# LPCXpresso55SXX_MCU.net
KiCad netlist of a schematic drawn in Altium Designer
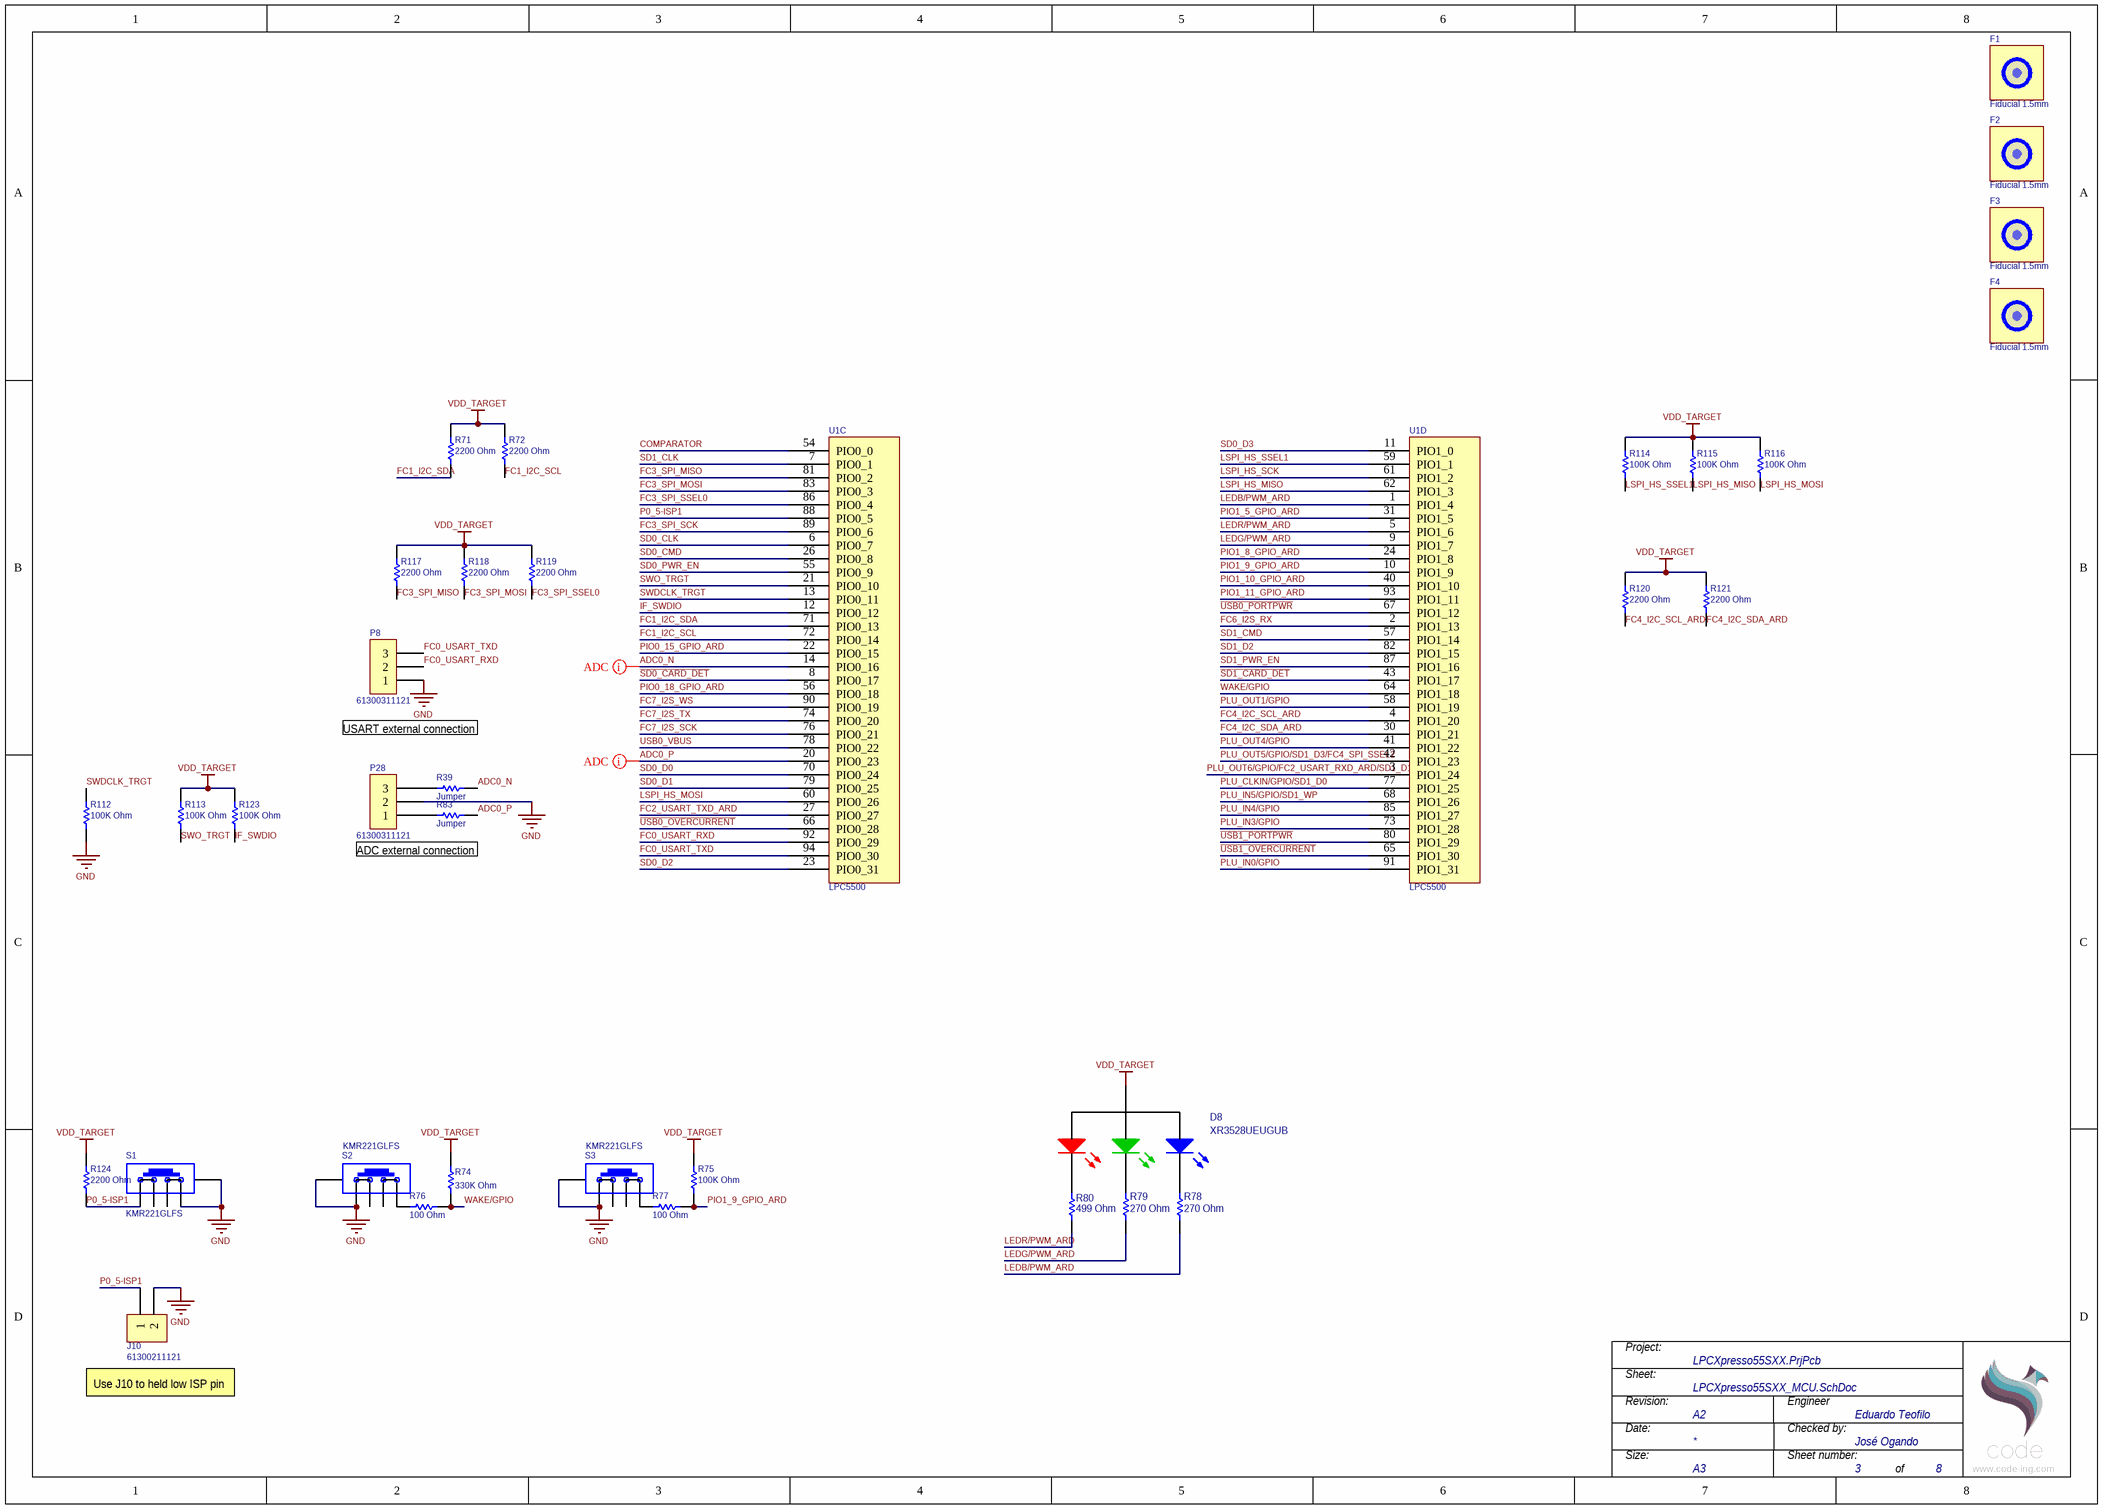
[diagram p0: LPCXpresso55SXX_MCU.SchDoc]

(export (version "E")
  (design (tool "Eeschema 10.0.6"))
  (components
    (comp (ref "D8")
      (value "XR3528UEUGUB")
      (footprint "XR3528UEUGUB")
      (description "LED RGB SMD DIFF 4-PLCC")
      (fields (field (name "CREATED BY") "cmartinez") (field (name "MODIFIED BY") "*"))
      (libsource (lib "LED Indication - Discrete") (part "XR3528UEUGUB"))
    )
    (comp (ref "F1")
      (value "Fiducial 1.5mm")
      (footprint "Fiducial 1.5mm")
      (fields (field (name "CREATED BY") "lsanchez") (field (name "MODIFIED BY") "*"))
      (libsource (lib "Fiducial") (part "Fiducial 1.5mm"))
    )
    (comp (ref "F2")
      (value "Fiducial 1.5mm")
      (footprint "Fiducial 1.5mm")
      (fields (field (name "CREATED BY") "lsanchez") (field (name "MODIFIED BY") "*"))
      (libsource (lib "Fiducial") (part "Fiducial 1.5mm"))
    )
    (comp (ref "F3")
      (value "Fiducial 1.5mm")
      (footprint "Fiducial 1.5mm")
      (fields (field (name "CREATED BY") "lsanchez") (field (name "MODIFIED BY") "*"))
      (libsource (lib "Fiducial") (part "Fiducial 1.5mm"))
    )
    (comp (ref "F4")
      (value "Fiducial 1.5mm")
      (footprint "Fiducial 1.5mm")
      (fields (field (name "CREATED BY") "lsanchez") (field (name "MODIFIED BY") "*"))
      (libsource (lib "Fiducial") (part "Fiducial 1.5mm"))
    )
    (comp (ref "J10")
      (value "61300211121")
      (footprint "61300211121")
      (description "HEADER 2POS SNGL T/H 2.54MM")
      (fields
        (field (name "MANUFACTURER") "Wurth Electronics Inc")
        (field (name "MODIFIED BY") "*")
        (field (name "CREATED BY") "gmoreno")
      )
      (libsource (lib "Rectangular - Headers, Male Pins") (part "61300211121"))
    )
    (comp (ref "P8")
      (value "61300311121")
      (footprint "61300311121")
      (description "HEADER 3POS SNGL T/H 2.54MM")
      (fields
        (field (name "MANUFACTURER") "Wurth Electronics Inc")
        (field (name "MODIFIED BY") "*")
        (field (name "CREATED BY") "gmoreno")
      )
      (libsource (lib "Rectangular - Headers, Male Pins") (part "61300311121"))
    )
    (comp (ref "P28")
      (value "61300311121")
      (footprint "61300311121")
      (description "HEADER 3POS SNGL T/H 2.54MM")
      (fields
        (field (name "MANUFACTURER") "Wurth Electronics Inc")
        (field (name "MODIFIED BY") "*")
        (field (name "CREATED BY") "gmoreno")
      )
      (libsource (lib "Rectangular - Headers, Male Pins") (part "61300311121"))
    )
    (comp (ref "R39")
      (value "Jumper")
      (footprint "RESC0402(1005)_L")
      (description "Jumper 0402 (1005 Metric)")
      (fields (field (name "TOLERANCE") "None"))
      (libsource (lib "Altium Content Vault") (part "CMP-1011-00001-1"))
    )
    (comp (ref "R71")
      (value "2200 Ohm")
      (footprint "RESC0402(1005)_L")
      (description "2K2 0.063W 1% 0402 (1005 Metric)  SMD")
      (fields (field (name "POWER") "0.063 W") (field (name "TOLERANCE") "1 %"))
      (libsource (lib "Altium Content Vault") (part "CMP-1011-00546-1"))
    )
    (comp (ref "R72")
      (value "2200 Ohm")
      (footprint "RESC0402(1005)_L")
      (description "2K2 0.063W 1% 0402 (1005 Metric)  SMD")
      (fields (field (name "POWER") "0.063 W") (field (name "TOLERANCE") "1 %"))
      (libsource (lib "Altium Content Vault") (part "CMP-1011-00546-1"))
    )
    (comp (ref "R74")
      (value "330K Ohm")
      (footprint "RESC0402(1005)_N")
      (description "330K 0.063W 1% 0402 (1005 Metric)  SMD")
      (fields (field (name "POWER") "0.063 W") (field (name "TOLERANCE") "1 %"))
      (libsource (lib "Altium Content Vault") (part "CMP-1011-00793-1"))
    )
    (comp (ref "R75")
      (value "100K Ohm")
      (footprint "RESC1005X40X25LL05T05")
      (description "Chip Resistor, 100 KOhm, +/- 1%, 100 mW, -55 to 155 degC, 0402 (1005 Metric), RoHS, Tape and Reel")
      (fields (field (name "TOLERANCE") "1%") (field (name "MANUFACTURER") "Basic Passives"))
      (libsource (lib "Altium Content Vault") (part "CMP-2002-00608-3"))
    )
    (comp (ref "R76")
      (value "100 Ohm")
      (footprint "RESC0402(1005)_L")
      (description "100R 0.063W 5% 0402 (1005 Metric)  SMD")
      (fields (field (name "POWER") "0.063 W") (field (name "TOLERANCE") "5 %"))
      (libsource (lib "Altium Content Vault") (part "CMP-1011-00050-1"))
    )
    (comp (ref "R77")
      (value "100 Ohm")
      (footprint "RESC0402(1005)_L")
      (description "100R 0.063W 5% 0402 (1005 Metric)  SMD")
      (fields (field (name "POWER") "0.063 W") (field (name "TOLERANCE") "5 %"))
      (libsource (lib "Altium Content Vault") (part "CMP-1011-00050-1"))
    )
    (comp (ref "R78")
      (value "270 Ohm")
      (footprint "RESC0402(1005)_L")
      (description "270R 0.063W 1% 0402 (1005 Metric)  SMD")
      (fields (field (name "TOLERANCE") "1 %") (field (name "POWER") "0.063 W"))
      (libsource (lib "Altium Content Vault") (part "CMP-1011-00444-1"))
    )
    (comp (ref "R79")
      (value "270 Ohm")
      (footprint "RESC0402(1005)_L")
      (description "270R 0.063W 1% 0402 (1005 Metric)  SMD")
      (fields (field (name "TOLERANCE") "1 %") (field (name "POWER") "0.063 W"))
      (libsource (lib "Altium Content Vault") (part "CMP-1011-00444-1"))
    )
    (comp (ref "R80")
      (value "499 Ohm")
      (footprint "RESC0402(1005)_L")
      (description "499R 0.063W 1% 0402 (1005 Metric)  SMD")
      (fields (field (name "TOLERANCE") "1 %") (field (name "POWER") "0.063 W"))
      (libsource (lib "Altium Content Vault") (part "CMP-1011-00476-1"))
    )
    (comp (ref "R83")
      (value "Jumper")
      (footprint "RESC0402(1005)_L")
      (description "Jumper 0402 (1005 Metric)")
      (fields (field (name "TOLERANCE") "None"))
      (libsource (lib "Altium Content Vault") (part "CMP-1011-00001-1"))
    )
    (comp (ref "R112")
      (value "100K Ohm")
      (footprint "RESC1005X40X25LL05T05")
      (description "Chip Resistor, 100 KOhm, +/- 1%, 100 mW, -55 to 155 degC, 0402 (1005 Metric), RoHS, Tape and Reel")
      (fields (field (name "TOLERANCE") "1%") (field (name "MANUFACTURER") "Basic Passives"))
      (libsource (lib "Altium Content Vault") (part "CMP-2002-00608-3"))
    )
    (comp (ref "R113")
      (value "100K Ohm")
      (footprint "RESC1005X40X25LL05T05")
      (description "Chip Resistor, 100 KOhm, +/- 1%, 100 mW, -55 to 155 degC, 0402 (1005 Metric), RoHS, Tape and Reel")
      (fields (field (name "TOLERANCE") "1%") (field (name "MANUFACTURER") "Basic Passives"))
      (libsource (lib "Altium Content Vault") (part "CMP-2002-00608-3"))
    )
    (comp (ref "R114")
      (value "100K Ohm")
      (footprint "RESC1005X40X25LL05T05")
      (description "Chip Resistor, 100 KOhm, +/- 1%, 100 mW, -55 to 155 degC, 0402 (1005 Metric), RoHS, Tape and Reel")
      (fields (field (name "TOLERANCE") "1%") (field (name "MANUFACTURER") "Basic Passives"))
      (libsource (lib "Altium Content Vault") (part "CMP-2002-00608-3"))
    )
    (comp (ref "R115")
      (value "100K Ohm")
      (footprint "RESC1005X40X25LL05T05")
      (description "Chip Resistor, 100 KOhm, +/- 1%, 100 mW, -55 to 155 degC, 0402 (1005 Metric), RoHS, Tape and Reel")
      (fields (field (name "TOLERANCE") "1%") (field (name "MANUFACTURER") "Basic Passives"))
      (libsource (lib "Altium Content Vault") (part "CMP-2002-00608-3"))
    )
    (comp (ref "R116")
      (value "100K Ohm")
      (footprint "RESC1005X40X25LL05T05")
      (description "Chip Resistor, 100 KOhm, +/- 1%, 100 mW, -55 to 155 degC, 0402 (1005 Metric), RoHS, Tape and Reel")
      (fields (field (name "TOLERANCE") "1%") (field (name "MANUFACTURER") "Basic Passives"))
      (libsource (lib "Altium Content Vault") (part "CMP-2002-00608-3"))
    )
    (comp (ref "R117")
      (value "2200 Ohm")
      (footprint "RESC0402(1005)_L")
      (description "2K2 0.063W 1% 0402 (1005 Metric)  SMD")
      (fields (field (name "POWER") "0.063 W") (field (name "TOLERANCE") "1 %"))
      (libsource (lib "Altium Content Vault") (part "CMP-1011-00546-1"))
    )
    (comp (ref "R118")
      (value "2200 Ohm")
      (footprint "RESC0402(1005)_L")
      (description "2K2 0.063W 1% 0402 (1005 Metric)  SMD")
      (fields (field (name "POWER") "0.063 W") (field (name "TOLERANCE") "1 %"))
      (libsource (lib "Altium Content Vault") (part "CMP-1011-00546-1"))
    )
    (comp (ref "R119")
      (value "2200 Ohm")
      (footprint "RESC0402(1005)_L")
      (description "2K2 0.063W 1% 0402 (1005 Metric)  SMD")
      (fields (field (name "POWER") "0.063 W") (field (name "TOLERANCE") "1 %"))
      (libsource (lib "Altium Content Vault") (part "CMP-1011-00546-1"))
    )
    (comp (ref "R120")
      (value "2200 Ohm")
      (footprint "RESC0402(1005)_L")
      (description "2K2 0.063W 1% 0402 (1005 Metric)  SMD")
      (fields (field (name "POWER") "0.063 W") (field (name "TOLERANCE") "1 %"))
      (libsource (lib "Altium Content Vault") (part "CMP-1011-00546-1"))
    )
    (comp (ref "R121")
      (value "2200 Ohm")
      (footprint "RESC0402(1005)_L")
      (description "2K2 0.063W 1% 0402 (1005 Metric)  SMD")
      (fields (field (name "POWER") "0.063 W") (field (name "TOLERANCE") "1 %"))
      (libsource (lib "Altium Content Vault") (part "CMP-1011-00546-1"))
    )
    (comp (ref "R123")
      (value "100K Ohm")
      (footprint "RESC1005X40X25LL05T05")
      (description "Chip Resistor, 100 KOhm, +/- 1%, 100 mW, -55 to 155 degC, 0402 (1005 Metric), RoHS, Tape and Reel")
      (fields (field (name "TOLERANCE") "1%") (field (name "MANUFACTURER") "Basic Passives"))
      (libsource (lib "Altium Content Vault") (part "CMP-2002-00608-3"))
    )
    (comp (ref "R124")
      (value "2200 Ohm")
      (footprint "RESC0402(1005)_L")
      (description "2K2 0.063W 1% 0402 (1005 Metric)  SMD")
      (fields (field (name "POWER") "0.063 W") (field (name "TOLERANCE") "1 %"))
      (libsource (lib "Altium Content Vault") (part "CMP-1011-00546-1"))
    )
    (comp (ref "S1")
      (value "KMR221GLFS")
      (footprint "KMR221GLFS")
      (description "SWITCH TACTILE SPST-NO 0.05A 32V")
      (fields
        (field (name "MANUFACTURER") "C&K")
        (field (name "CREATED BY") "eteofilo")
        (field (name "MODIFIED BY") "*")
      )
      (libsource (lib "Tactile") (part "KMR221GLFS"))
    )
    (comp (ref "S2")
      (value "KMR221GLFS")
      (footprint "KMR221GLFS")
      (description "SWITCH TACTILE SPST-NO 0.05A 32V")
      (fields
        (field (name "MANUFACTURER") "C&K")
        (field (name "CREATED BY") "eteofilo")
        (field (name "MODIFIED BY") "*")
      )
      (libsource (lib "") (part "KMR221GLFS_1"))
    )
    (comp (ref "S3")
      (value "KMR221GLFS")
      (footprint "KMR221GLFS")
      (description "SWITCH TACTILE SPST-NO 0.05A 32V")
      (fields
        (field (name "MANUFACTURER") "C&K")
        (field (name "CREATED BY") "eteofilo")
        (field (name "MODIFIED BY") "*")
      )
      (libsource (lib "") (part "KMR221GLFS_1"))
    )
    (comp (ref "U1")
      (value "LPC5500")
      (footprint "LQFP EP 100")
      (description "32-bit ARM Cortex-M33, 312 KB SRAM, LPC55XX Series")
      (fields
        (field (name "MANUFACTURER") "NXP")
        (field (name "CREATED BY") "eteofilo")
        (field (name "MODIFIED BY") "*")
      )
      (libsource (lib "Embedded - Microcontrollers") (part "LPC5500"))
    )
  )
  (nets
    (net (code "1") (name "/ADC0_N") (class "Default")
      (node (ref "R39") (pin "1") (pinfunction "1_1") (pintype "passive"))
      (node (ref "U1") (pin "14") (pinfunction "PIO0_16_14") (pintype "passive"))
    )
    (net (code "2") (name "/ADC0_P") (class "Default")
      (node (ref "R83") (pin "1") (pinfunction "1_1") (pintype "passive"))
      (node (ref "U1") (pin "20") (pinfunction "PIO0_23_20") (pintype "passive"))
    )
    (net (code "3") (name "/COMPARATOR") (class "Default")
      (node (ref "U1") (pin "54") (pinfunction "PIO0_0_54") (pintype "passive"))
    )
    (net (code "4") (name "/FC0_USART_RXD") (class "Default")
      (node (ref "P8") (pin "2") (pinfunction "2_2") (pintype "passive"))
      (node (ref "U1") (pin "92") (pinfunction "PIO0_29_92") (pintype "passive"))
    )
    (net (code "5") (name "/FC0_USART_TXD") (class "Default")
      (node (ref "P8") (pin "3") (pinfunction "3_3") (pintype "passive"))
      (node (ref "U1") (pin "94") (pinfunction "PIO0_30_94") (pintype "passive"))
    )
    (net (code "6") (name "/FC1_I2C_SCL") (class "Default")
      (node (ref "R72") (pin "1") (pinfunction "1_1") (pintype "passive"))
      (node (ref "U1") (pin "72") (pinfunction "PIO0_14_72") (pintype "passive"))
    )
    (net (code "7") (name "/FC1_I2C_SDA") (class "Default")
      (node (ref "R71") (pin "1") (pinfunction "1_1") (pintype "passive"))
      (node (ref "U1") (pin "71") (pinfunction "PIO0_13_71") (pintype "passive"))
    )
    (net (code "8") (name "/FC2_USART_TXD_ARD") (class "Default")
      (node (ref "U1") (pin "27") (pinfunction "PIO0_27_27") (pintype "passive"))
    )
    (net (code "9") (name "/FC3_SPI_MISO") (class "Default")
      (node (ref "R117") (pin "1") (pinfunction "1_1") (pintype "passive"))
      (node (ref "U1") (pin "81") (pinfunction "PIO0_2_81") (pintype "passive"))
    )
    (net (code "10") (name "/FC3_SPI_MOSI") (class "Default")
      (node (ref "R118") (pin "1") (pinfunction "1_1") (pintype "passive"))
      (node (ref "U1") (pin "83") (pinfunction "PIO0_3_83") (pintype "passive"))
    )
    (net (code "11") (name "/FC3_SPI_SCK") (class "Default")
      (node (ref "U1") (pin "89") (pinfunction "PIO0_6_89") (pintype "passive"))
    )
    (net (code "12") (name "/FC3_SPI_SSEL0") (class "Default")
      (node (ref "R119") (pin "1") (pinfunction "1_1") (pintype "passive"))
      (node (ref "U1") (pin "86") (pinfunction "PIO0_4_86") (pintype "passive"))
    )
    (net (code "13") (name "/FC4_I2C_SCL_ARD") (class "Default")
      (node (ref "R120") (pin "1") (pinfunction "1_1") (pintype "passive"))
      (node (ref "U1") (pin "4") (pinfunction "PIO1_20_4") (pintype "passive"))
    )
    (net (code "14") (name "/FC4_I2C_SDA_ARD") (class "Default")
      (node (ref "R121") (pin "1") (pinfunction "1_1") (pintype "passive"))
      (node (ref "U1") (pin "30") (pinfunction "PIO1_21_30") (pintype "passive"))
    )
    (net (code "15") (name "/FC6_I2S_RX") (class "Default")
      (node (ref "U1") (pin "2") (pinfunction "PIO1_13_2") (pintype "passive"))
    )
    (net (code "16") (name "/FC7_I2S_SCK") (class "Default")
      (node (ref "U1") (pin "76") (pinfunction "PIO0_21_76") (pintype "passive"))
    )
    (net (code "17") (name "/FC7_I2S_TX") (class "Default")
      (node (ref "U1") (pin "74") (pinfunction "PIO0_20_74") (pintype "passive"))
    )
    (net (code "18") (name "/FC7_I2S_WS") (class "Default")
      (node (ref "U1") (pin "90") (pinfunction "PIO0_19_90") (pintype "passive"))
    )
    (net (code "19") (name "/IF_SWDIO") (class "Default")
      (node (ref "R123") (pin "1") (pinfunction "1_1") (pintype "passive"))
      (node (ref "U1") (pin "12") (pinfunction "PIO0_12_12") (pintype "passive"))
    )
    (net (code "20") (name "/LEDB{slash}PWM_ARD") (class "Default")
      (node (ref "R78") (pin "1") (pinfunction "1_1") (pintype "passive"))
      (node (ref "U1") (pin "1") (pinfunction "PIO1_4_1") (pintype "passive"))
    )
    (net (code "21") (name "/LEDG{slash}PWM_ARD") (class "Default")
      (node (ref "R79") (pin "1") (pinfunction "1_1") (pintype "passive"))
      (node (ref "U1") (pin "9") (pinfunction "PIO1_7_9") (pintype "passive"))
    )
    (net (code "22") (name "/LEDR{slash}PWM_ARD") (class "Default")
      (node (ref "R80") (pin "1") (pinfunction "1_1") (pintype "passive"))
      (node (ref "U1") (pin "5") (pinfunction "PIO1_6_5") (pintype "passive"))
    )
    (net (code "23") (name "/LSPI_HS_MISO") (class "Default")
      (node (ref "R115") (pin "1") (pinfunction "1_1") (pintype "passive"))
      (node (ref "U1") (pin "62") (pinfunction "PIO1_3_62") (pintype "passive"))
    )
    (net (code "24") (name "/LSPI_HS_MOSI") (class "Default")
      (node (ref "R116") (pin "1") (pinfunction "1_1") (pintype "passive"))
      (node (ref "U1") (pin "60") (pinfunction "PIO0_26_60") (pintype "passive"))
    )
    (net (code "25") (name "/LSPI_HS_SCK") (class "Default")
      (node (ref "U1") (pin "61") (pinfunction "PIO1_2_61") (pintype "passive"))
    )
    (net (code "26") (name "/LSPI_HS_SSEL1") (class "Default")
      (node (ref "R114") (pin "1") (pinfunction "1_1") (pintype "passive"))
      (node (ref "U1") (pin "59") (pinfunction "PIO1_1_59") (pintype "passive"))
    )
    (net (code "27") (name "/P0_5-ISP1") (class "Default")
      (node (ref "J10") (pin "1") (pinfunction "1_1") (pintype "passive"))
      (node (ref "R124") (pin "2") (pinfunction "2_2") (pintype "passive"))
      (node (ref "S1") (pin "1") (pinfunction "1_1") (pintype "passive"))
      (node (ref "U1") (pin "88") (pinfunction "PIO0_5_88") (pintype "passive"))
    )
    (net (code "28") (name "/PIO0_15_GPIO_ARD") (class "Default")
      (node (ref "U1") (pin "22") (pinfunction "PIO0_15_22") (pintype "passive"))
    )
    (net (code "29") (name "/PIO0_18_GPIO_ARD") (class "Default")
      (node (ref "U1") (pin "56") (pinfunction "PIO0_18_56") (pintype "passive"))
    )
    (net (code "30") (name "/PIO1_5_GPIO_ARD") (class "Default")
      (node (ref "U1") (pin "31") (pinfunction "PIO1_5_31") (pintype "passive"))
    )
    (net (code "31") (name "/PIO1_8_GPIO_ARD") (class "Default")
      (node (ref "U1") (pin "24") (pinfunction "PIO1_8_24") (pintype "passive"))
    )
    (net (code "32") (name "/PIO1_9_GPIO_ARD") (class "Default")
      (node (ref "R75") (pin "1") (pinfunction "1_1") (pintype "passive"))
      (node (ref "R77") (pin "2") (pinfunction "2_2") (pintype "passive"))
      (node (ref "U1") (pin "10") (pinfunction "PIO1_9_10") (pintype "passive"))
    )
    (net (code "33") (name "/PIO1_10_GPIO_ARD") (class "Default")
      (node (ref "U1") (pin "40") (pinfunction "PIO1_10_40") (pintype "passive"))
    )
    (net (code "34") (name "/PIO1_11_GPIO_ARD") (class "Default")
      (node (ref "U1") (pin "93") (pinfunction "PIO1_11_93") (pintype "passive"))
    )
    (net (code "35") (name "/PLU_CLKIN{slash}GPIO{slash}SD1_D0") (class "Default")
      (node (ref "U1") (pin "77") (pinfunction "PIO1_25_77") (pintype "passive"))
    )
    (net (code "36") (name "/PLU_IN0{slash}GPIO") (class "Default")
      (node (ref "U1") (pin "91") (pinfunction "PIO1_31_91") (pintype "passive"))
    )
    (net (code "37") (name "/PLU_IN3{slash}GPIO") (class "Default")
      (node (ref "U1") (pin "73") (pinfunction "PIO1_28_73") (pintype "passive"))
    )
    (net (code "38") (name "/PLU_IN4{slash}GPIO") (class "Default")
      (node (ref "U1") (pin "85") (pinfunction "PIO1_27_85") (pintype "passive"))
    )
    (net (code "39") (name "/PLU_IN5{slash}GPIO{slash}SD1_WP") (class "Default")
      (node (ref "U1") (pin "68") (pinfunction "PIO1_26_68") (pintype "passive"))
    )
    (net (code "40") (name "/PLU_OUT1{slash}GPIO") (class "Default")
      (node (ref "U1") (pin "58") (pinfunction "PIO1_19_58") (pintype "passive"))
    )
    (net (code "41") (name "/PLU_OUT4{slash}GPIO") (class "Default")
      (node (ref "U1") (pin "41") (pinfunction "PIO1_22_41") (pintype "passive"))
    )
    (net (code "42") (name "/PLU_OUT5{slash}GPIO{slash}SD1_D3{slash}FC4_SPI_SSEL2") (class "Default")
      (node (ref "U1") (pin "42") (pinfunction "PIO1_23_42") (pintype "passive"))
    )
    (net (code "43") (name "/PLU_OUT6{slash}GPIO{slash}FC2_USART_RXD_ARD{slash}SD1_D1") (class "Default")
      (node (ref "U1") (pin "3") (pinfunction "PIO1_24_3") (pintype "passive"))
    )
    (net (code "44") (name "/SD0_CLK") (class "Default")
      (node (ref "U1") (pin "6") (pinfunction "PIO0_7_6") (pintype "passive"))
    )
    (net (code "45") (name "/SD0_CMD") (class "Default")
      (node (ref "U1") (pin "26") (pinfunction "PIO0_8_26") (pintype "passive"))
    )
    (net (code "46") (name "/SD0_D0") (class "Default")
      (node (ref "U1") (pin "70") (pinfunction "PIO0_24_70") (pintype "passive"))
    )
    (net (code "47") (name "/SD0_D1") (class "Default")
      (node (ref "U1") (pin "79") (pinfunction "PIO0_25_79") (pintype "passive"))
    )
    (net (code "48") (name "/SD0_D2") (class "Default")
      (node (ref "U1") (pin "23") (pinfunction "PIO0_31_23") (pintype "passive"))
    )
    (net (code "49") (name "/SD0_D3") (class "Default")
      (node (ref "U1") (pin "11") (pinfunction "PIO1_0_11") (pintype "passive"))
    )
    (net (code "50") (name "/SD0_PWR_EN") (class "Default")
      (node (ref "U1") (pin "55") (pinfunction "PIO0_9_55") (pintype "passive"))
    )
    (net (code "51") (name "/SD1_CLK") (class "Default")
      (node (ref "U1") (pin "7") (pinfunction "PIO0_1_7") (pintype "passive"))
    )
    (net (code "52") (name "/SD1_CMD") (class "Default")
      (node (ref "U1") (pin "57") (pinfunction "PIO1_14_57") (pintype "passive"))
    )
    (net (code "53") (name "/SD1_D2") (class "Default")
      (node (ref "U1") (pin "82") (pinfunction "PIO1_15_82") (pintype "passive"))
    )
    (net (code "54") (name "/SD1_PWR_EN") (class "Default")
      (node (ref "U1") (pin "87") (pinfunction "PIO1_16_87") (pintype "passive"))
    )
    (net (code "55") (name "/SWDCLK_TRGT") (class "Default")
      (node (ref "R112") (pin "2") (pinfunction "2_2") (pintype "passive"))
      (node (ref "U1") (pin "13") (pinfunction "PIO0_11_13") (pintype "passive"))
    )
    (net (code "56") (name "/SWO_TRGT") (class "Default")
      (node (ref "R113") (pin "1") (pinfunction "1_1") (pintype "passive"))
      (node (ref "U1") (pin "21") (pinfunction "PIO0_10_21") (pintype "passive"))
    )
    (net (code "57") (name "/USB0_VBUS") (class "Default")
      (node (ref "U1") (pin "78") (pinfunction "PIO0_22_78") (pintype "passive"))
    )
    (net (code "58") (name "/WAKE{slash}GPIO") (class "Default")
      (node (ref "R74") (pin "1") (pinfunction "1_1") (pintype "passive"))
      (node (ref "R76") (pin "2") (pinfunction "2_2") (pintype "passive"))
      (node (ref "U1") (pin "64") (pinfunction "PIO1_18_64") (pintype "passive"))
    )
    (net (code "59") (name "/~{SD0_CARD_DET}") (class "Default")
      (node (ref "U1") (pin "8") (pinfunction "PIO0_17_8") (pintype "passive"))
    )
    (net (code "60") (name "/~{SD1_CARD_DET}") (class "Default")
      (node (ref "U1") (pin "43") (pinfunction "PIO1_17_43") (pintype "passive"))
    )
    (net (code "61") (name "/~{USB0_OVERCURRENT}") (class "Default")
      (node (ref "U1") (pin "66") (pinfunction "PIO0_28_66") (pintype "passive"))
    )
    (net (code "62") (name "/~{USB0_PORTPWR}") (class "Default")
      (node (ref "U1") (pin "67") (pinfunction "PIO1_12_67") (pintype "passive"))
    )
    (net (code "63") (name "/~{USB1_OVERCURRENT}") (class "Default")
      (node (ref "U1") (pin "65") (pinfunction "PIO1_30_65") (pintype "passive"))
    )
    (net (code "64") (name "/~{USB1_PORTPWR}") (class "Default")
      (node (ref "U1") (pin "80") (pinfunction "PIO1_29_80") (pintype "passive"))
    )
    (net (code "65") (name "GND") (class "Default")
      (node (ref "J10") (pin "2") (pinfunction "2_2") (pintype "passive"))
      (node (ref "P28") (pin "2") (pinfunction "2_2") (pintype "passive"))
      (node (ref "P8") (pin "1") (pinfunction "1_1") (pintype "passive"))
      (node (ref "R112") (pin "1") (pinfunction "1_1") (pintype "passive"))
      (node (ref "S1") (pin "2") (pinfunction "2_2") (pintype "passive"))
      (node (ref "S1") (pin "5") (pinfunction "5_5") (pintype "passive"))
      (node (ref "S2") (pin "2") (pinfunction "2_2") (pintype "passive"))
      (node (ref "S2") (pin "5") (pinfunction "5_5") (pintype "passive"))
      (node (ref "S3") (pin "2") (pinfunction "2_2") (pintype "passive"))
      (node (ref "S3") (pin "5") (pinfunction "5_5") (pintype "passive"))
    )
    (net (code "66") (name "Net-(D8-Pad1)") (class "Default")
      (node (ref "D8") (pin "1") (pinfunction "1_1") (pintype "passive"))
      (node (ref "R78") (pin "2") (pinfunction "2_2") (pintype "passive"))
    )
    (net (code "67") (name "Net-(D8-Pad3)") (class "Default")
      (node (ref "D8") (pin "3") (pinfunction "3_3") (pintype "passive"))
      (node (ref "R80") (pin "2") (pinfunction "2_2") (pintype "passive"))
    )
    (net (code "68") (name "Net-(D8-Pad4)") (class "Default")
      (node (ref "D8") (pin "4") (pinfunction "4_4") (pintype "passive"))
      (node (ref "R79") (pin "2") (pinfunction "2_2") (pintype "passive"))
    )
    (net (code "69") (name "Net-(P28-Pad1)") (class "Default")
      (node (ref "P28") (pin "1") (pinfunction "1_1") (pintype "passive"))
      (node (ref "R83") (pin "2") (pinfunction "2_2") (pintype "passive"))
    )
    (net (code "70") (name "Net-(P28-Pad3)") (class "Default")
      (node (ref "P28") (pin "3") (pinfunction "3_3") (pintype "passive"))
      (node (ref "R39") (pin "2") (pinfunction "2_2") (pintype "passive"))
    )
    (net (code "71") (name "Net-(R76-Pad1)") (class "Default")
      (node (ref "R76") (pin "1") (pinfunction "1_1") (pintype "passive"))
      (node (ref "S2") (pin "1") (pinfunction "1_1") (pintype "passive"))
    )
    (net (code "72") (name "Net-(R77-Pad1)") (class "Default")
      (node (ref "R77") (pin "1") (pinfunction "1_1") (pintype "passive"))
      (node (ref "S3") (pin "1") (pinfunction "1_1") (pintype "passive"))
    )
    (net (code "73") (name "VDD_TARGET") (class "Default")
      (node (ref "D8") (pin "2") (pinfunction "2_2") (pintype "passive"))
      (node (ref "R113") (pin "2") (pinfunction "2_2") (pintype "passive"))
      (node (ref "R114") (pin "2") (pinfunction "2_2") (pintype "passive"))
      (node (ref "R115") (pin "2") (pinfunction "2_2") (pintype "passive"))
      (node (ref "R116") (pin "2") (pinfunction "2_2") (pintype "passive"))
      (node (ref "R117") (pin "2") (pinfunction "2_2") (pintype "passive"))
      (node (ref "R118") (pin "2") (pinfunction "2_2") (pintype "passive"))
      (node (ref "R119") (pin "2") (pinfunction "2_2") (pintype "passive"))
      (node (ref "R120") (pin "2") (pinfunction "2_2") (pintype "passive"))
      (node (ref "R121") (pin "2") (pinfunction "2_2") (pintype "passive"))
      (node (ref "R123") (pin "2") (pinfunction "2_2") (pintype "passive"))
      (node (ref "R124") (pin "1") (pinfunction "1_1") (pintype "passive"))
      (node (ref "R71") (pin "2") (pinfunction "2_2") (pintype "passive"))
      (node (ref "R72") (pin "2") (pinfunction "2_2") (pintype "passive"))
      (node (ref "R74") (pin "2") (pinfunction "2_2") (pintype "passive"))
      (node (ref "R75") (pin "2") (pinfunction "2_2") (pintype "passive"))
    )
    (net (code "74") (name "unconnected-(F1-Pad1)") (class "Default")
      (node (ref "F1") (pin "1") (pinfunction "1_1") (pintype "passive"))
    )
    (net (code "75") (name "unconnected-(F2-Pad1)") (class "Default")
      (node (ref "F2") (pin "1") (pinfunction "1_1") (pintype "passive"))
    )
    (net (code "76") (name "unconnected-(F3-Pad1)") (class "Default")
      (node (ref "F3") (pin "1") (pinfunction "1_1") (pintype "passive"))
    )
    (net (code "77") (name "unconnected-(F4-Pad1)") (class "Default")
      (node (ref "F4") (pin "1") (pinfunction "1_1") (pintype "passive"))
    )
    (net (code "78") (name "unconnected-(S1-Pad3)") (class "Default")
      (node (ref "S1") (pin "3") (pinfunction "3_3") (pintype "passive"))
    )
    (net (code "79") (name "unconnected-(S1-Pad4)") (class "Default")
      (node (ref "S1") (pin "4") (pinfunction "4_4") (pintype "passive"))
    )
    (net (code "80") (name "unconnected-(S2-Pad3)") (class "Default")
      (node (ref "S2") (pin "3") (pinfunction "3_3") (pintype "passive"))
    )
    (net (code "81") (name "unconnected-(S2-Pad4)") (class "Default")
      (node (ref "S2") (pin "4") (pinfunction "4_4") (pintype "passive"))
    )
    (net (code "82") (name "unconnected-(S3-Pad3)") (class "Default")
      (node (ref "S3") (pin "3") (pinfunction "3_3") (pintype "passive"))
    )
    (net (code "83") (name "unconnected-(S3-Pad4)") (class "Default")
      (node (ref "S3") (pin "4") (pinfunction "4_4") (pintype "passive"))
    )
  )
)
